# SparkFun_Buck_Regulator_-_AP63203.net
KiCad netlist of a schematic drawn in EAGLE
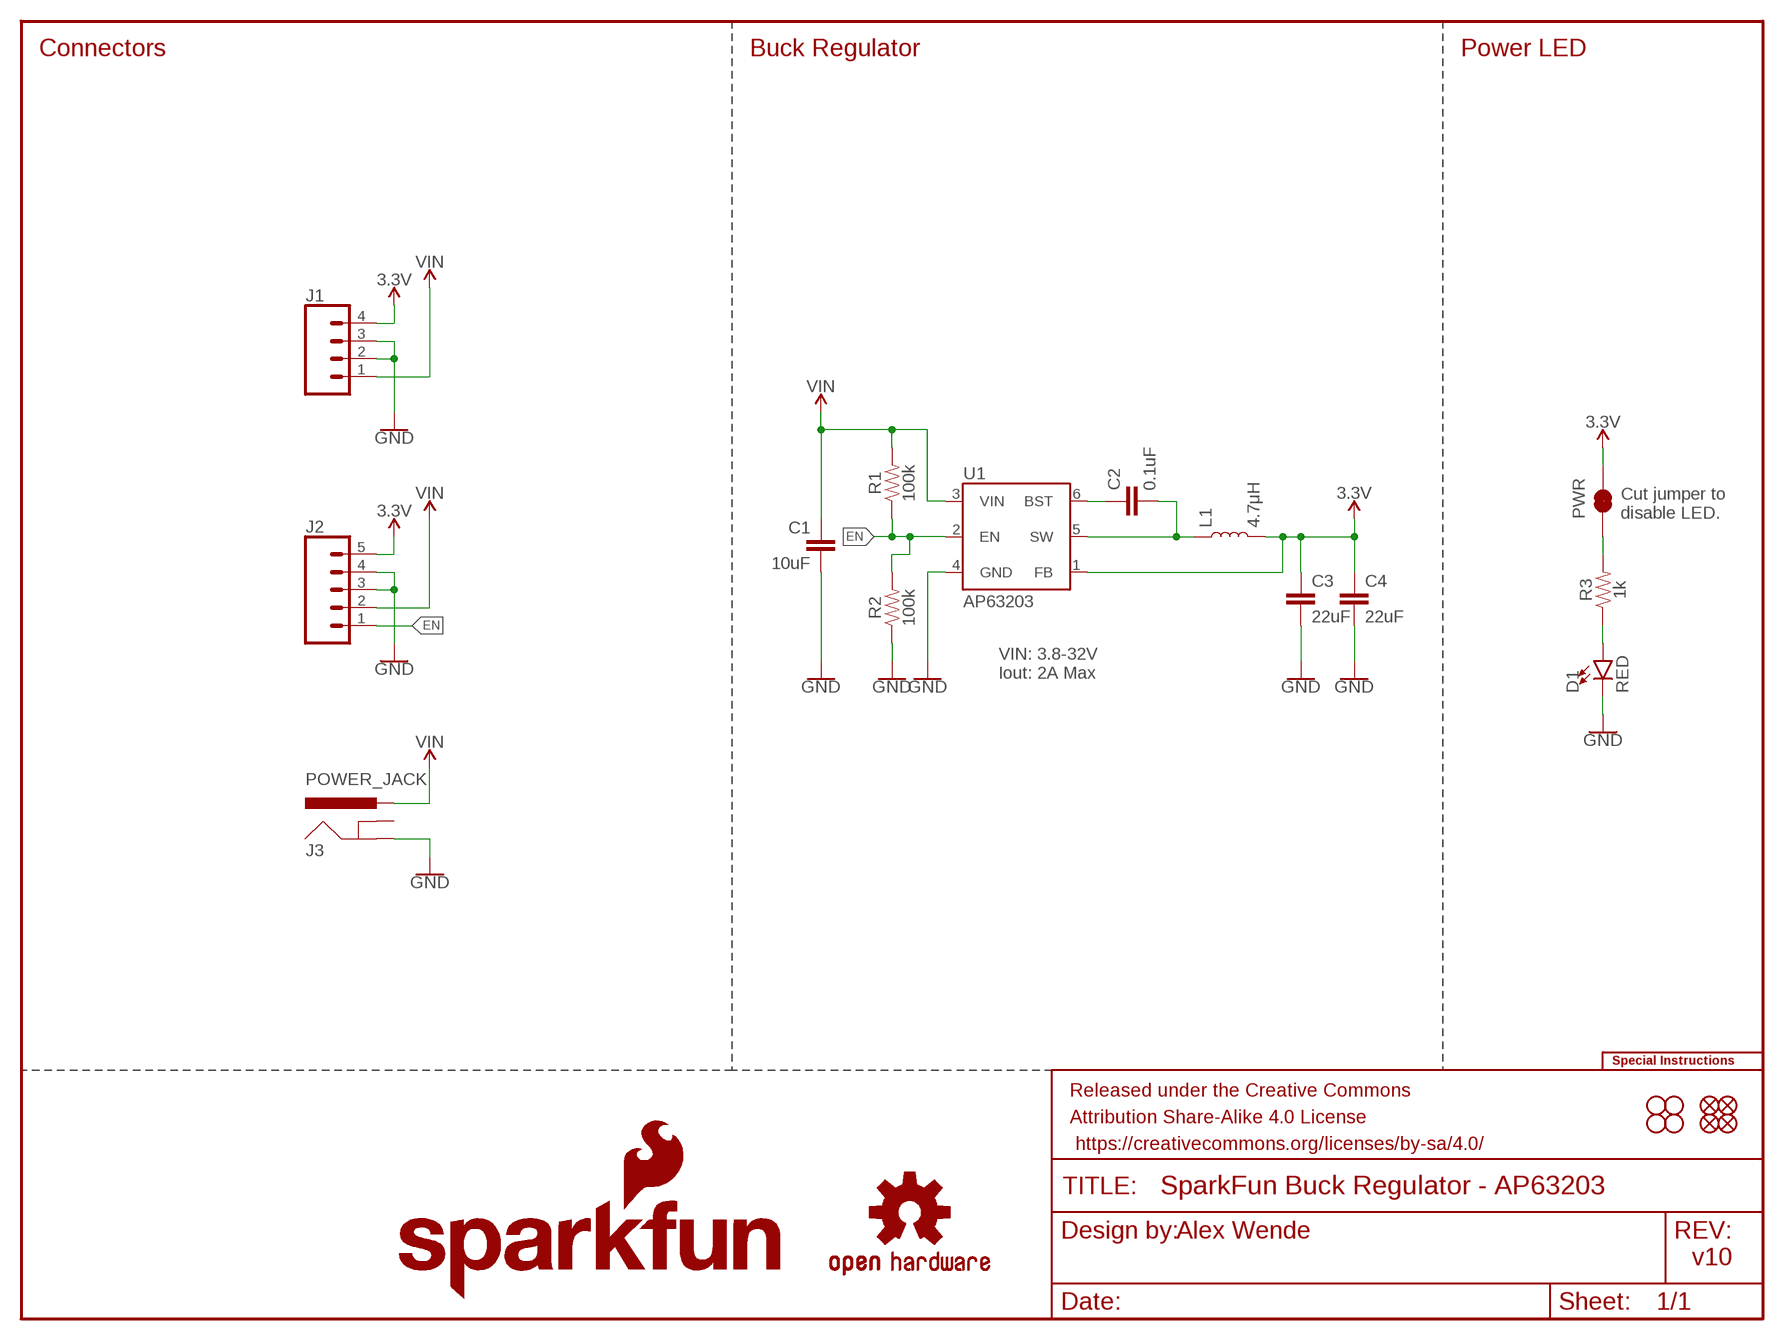
[diagram p0: schematic, sheet 1]

(export (version "E")
  (design (tool "Eeschema 10.0.6"))
  (components
    (comp (ref "C1")
      (value "10uF")
      (footprint "eagle-import:1210")
      (libsource (lib "eagle-import") (part "10UF-1210-50V-20%"))
    )
    (comp (ref "C2")
      (value "0.1uF")
      (footprint "eagle-import:0603")
      (libsource (lib "eagle-import") (part "0.1UF-0603-25V-5%"))
    )
    (comp (ref "C3")
      (value "22uF")
      (footprint "eagle-import:0603")
      (libsource (lib "eagle-import") (part "22UF-0603-6.3V-20%"))
    )
    (comp (ref "C4")
      (value "22uF")
      (footprint "eagle-import:0603")
      (libsource (lib "eagle-import") (part "22UF-0603-6.3V-20%"))
    )
    (comp (ref "D1")
      (value "RED")
      (footprint "eagle-import:LED-0603")
      (libsource (lib "eagle-import") (part "LED-RED0603"))
    )
    (comp (ref "FD1")
      (value "FIDUCIALUFIDUCIAL")
      (footprint "eagle-import:FIDUCIAL-MICRO")
      (libsource (lib "eagle-import") (part "FIDUCIALUFIDUCIAL"))
    )
    (comp (ref "FD2")
      (value "FIDUCIALUFIDUCIAL")
      (footprint "eagle-import:FIDUCIAL-MICRO")
      (libsource (lib "eagle-import") (part "FIDUCIALUFIDUCIAL"))
    )
    (comp (ref "FD3")
      (value "FIDUCIALUFIDUCIAL")
      (footprint "eagle-import:FIDUCIAL-MICRO")
      (libsource (lib "eagle-import") (part "FIDUCIALUFIDUCIAL"))
    )
    (comp (ref "FD4")
      (value "FIDUCIALUFIDUCIAL")
      (footprint "eagle-import:FIDUCIAL-MICRO")
      (libsource (lib "eagle-import") (part "FIDUCIALUFIDUCIAL"))
    )
    (comp (ref "FRAME1")
      (value "FRAME-LETTER")
      (footprint "eagle-import:CREATIVE_COMMONS")
      (libsource (lib "eagle-import") (part "FRAME-LETTER"))
    )
    (comp (ref "H1")
      (value "STAND-OFF")
      (footprint "eagle-import:STAND-OFF")
      (libsource (lib "eagle-import") (part "STAND-OFF"))
    )
    (comp (ref "H2")
      (value "STAND-OFF")
      (footprint "eagle-import:STAND-OFF")
      (libsource (lib "eagle-import") (part "STAND-OFF"))
    )
    (comp (ref "H3")
      (value "STAND-OFF")
      (footprint "eagle-import:STAND-OFF")
      (libsource (lib "eagle-import") (part "STAND-OFF"))
    )
    (comp (ref "H4")
      (value "STAND-OFF")
      (footprint "eagle-import:STAND-OFF")
      (libsource (lib "eagle-import") (part "STAND-OFF"))
    )
    (comp (ref "J1")
      (value "CONN_04SCREW")
      (footprint "eagle-import:SCREWTERMINAL-3.5MM-4")
      (libsource (lib "eagle-import") (part "CONN_04SCREW"))
    )
    (comp (ref "J2")
      (value "CONN_05NO_SILK")
      (footprint "eagle-import:1X05_NO_SILK")
      (libsource (lib "eagle-import") (part "CONN_05NO_SILK"))
    )
    (comp (ref "J3")
      (value "POWER_JACK")
      (footprint "eagle-import:POWER_JACK_PTH_SLOT")
      (libsource (lib "eagle-import") (part "POWER_JACKPOWER_JACK_SLOT"))
    )
    (comp (ref "L1")
      (value "4.7μH")
      (footprint "eagle-import:INDUCTOR_4X4MM")
      (libsource (lib "eagle-import") (part "4.7μH_SHIELDED_INDUCTORNPIS_LS"))
    )
    (comp (ref "LOGO1")
      (value "SFE_LOGO_NAME_FLAME.1_INCH")
      (footprint "eagle-import:SFE_LOGO_NAME_FLAME_.1")
      (libsource (lib "eagle-import") (part "SFE_LOGO_NAME_FLAME.1_INCH"))
    )
    (comp (ref "LOGO2")
      (value "OSHW-LOGOS")
      (footprint "eagle-import:OSHW-LOGO-S")
      (libsource (lib "eagle-import") (part "OSHW-LOGOS"))
    )
    (comp (ref "LOGO3")
      (value "SPECIAL_INSTRUCTIONS-ORDERING")
      (footprint "eagle-import:ORDERING_INSTRUCTIONS")
      (libsource (lib "eagle-import") (part "SPECIAL_INSTRUCTIONS-ORDERING"))
    )
    (comp (ref "PWR")
      (value "JUMPER-SMT_2_NC_TRACE_SILK")
      (footprint "eagle-import:SMT-JUMPER_2_NC_TRACE_SILK")
      (libsource (lib "eagle-import") (part "JUMPER-SMT_2_NC_TRACE_SILK"))
    )
    (comp (ref "R1")
      (value "100k")
      (footprint "eagle-import:0603")
      (libsource (lib "eagle-import") (part "100KOHM-0603-1/10W-1%"))
    )
    (comp (ref "R2")
      (value "100k")
      (footprint "eagle-import:0603")
      (libsource (lib "eagle-import") (part "100KOHM-0603-1/10W-1%"))
    )
    (comp (ref "R3")
      (value "1k")
      (footprint "eagle-import:0603")
      (libsource (lib "eagle-import") (part "1KOHM-0603-1/10W-1%"))
    )
    (comp (ref "U1")
      (value "AP63203")
      (footprint "eagle-import:SOT23-6")
      (libsource (lib "eagle-import") (part "AP63203"))
    )
  )
  (nets
    (net (code "1") (name "3.3V") (class "Default")
      (node (ref "C3") (pin "1") (pinfunction "1_1") (pintype "passive"))
      (node (ref "C4") (pin "1") (pinfunction "1_1") (pintype "passive"))
      (node (ref "J1") (pin "4") (pinfunction "4_4") (pintype "passive"))
      (node (ref "J2") (pin "5") (pinfunction "5_5") (pintype "passive"))
      (node (ref "L1") (pin "P$2") (pinfunction "2_P$2") (pintype "passive"))
      (node (ref "PWR") (pin "2") (pinfunction "2_2") (pintype "passive"))
      (node (ref "U1") (pin "1") (pinfunction "FB_1") (pintype "bidirectional"))
    )
    (net (code "2") (name "EN") (class "Default")
      (node (ref "J2") (pin "1") (pinfunction "1_1") (pintype "passive"))
      (node (ref "R1") (pin "1") (pinfunction "1_1") (pintype "passive"))
      (node (ref "R2") (pin "2") (pinfunction "2_2") (pintype "passive"))
      (node (ref "U1") (pin "2") (pinfunction "EN_2") (pintype "bidirectional"))
    )
    (net (code "3") (name "GND") (class "Default")
      (node (ref "C1") (pin "2") (pinfunction "2_2") (pintype "passive"))
      (node (ref "C3") (pin "2") (pinfunction "2_2") (pintype "passive"))
      (node (ref "C4") (pin "2") (pinfunction "2_2") (pintype "passive"))
      (node (ref "D1") (pin "C") (pinfunction "C_C") (pintype "passive"))
      (node (ref "J1") (pin "2") (pinfunction "2_2") (pintype "passive"))
      (node (ref "J1") (pin "3") (pinfunction "3_3") (pintype "passive"))
      (node (ref "J2") (pin "3") (pinfunction "3_3") (pintype "passive"))
      (node (ref "J2") (pin "4") (pinfunction "4_4") (pintype "passive"))
      (node (ref "J3") (pin "GND") (pinfunction "GND_GND") (pintype "bidirectional"))
      (node (ref "R2") (pin "1") (pinfunction "1_1") (pintype "passive"))
      (node (ref "U1") (pin "4") (pinfunction "GND_4") (pintype "bidirectional"))
    )
    (net (code "4") (name "Net-(D1-PadA)") (class "Default")
      (node (ref "D1") (pin "A") (pinfunction "A_A") (pintype "passive"))
      (node (ref "R3") (pin "1") (pinfunction "1_1") (pintype "passive"))
    )
    (net (code "5") (name "Net-(L1-1)") (class "Default")
      (node (ref "C2") (pin "2") (pinfunction "2_2") (pintype "passive"))
      (node (ref "L1") (pin "P$1") (pinfunction "1_P$1") (pintype "passive"))
      (node (ref "U1") (pin "5") (pinfunction "SW_5") (pintype "bidirectional"))
    )
    (net (code "6") (name "Net-(PWR-Pad1)") (class "Default")
      (node (ref "PWR") (pin "1") (pinfunction "1_1") (pintype "passive"))
      (node (ref "R3") (pin "2") (pinfunction "2_2") (pintype "passive"))
    )
    (net (code "7") (name "Net-(U1-BST)") (class "Default")
      (node (ref "C2") (pin "1") (pinfunction "1_1") (pintype "passive"))
      (node (ref "U1") (pin "6") (pinfunction "BST_6") (pintype "bidirectional"))
    )
    (net (code "8") (name "VIN") (class "Default")
      (node (ref "C1") (pin "1") (pinfunction "1_1") (pintype "passive"))
      (node (ref "J1") (pin "1") (pinfunction "1_1") (pintype "passive"))
      (node (ref "J2") (pin "2") (pinfunction "2_2") (pintype "passive"))
      (node (ref "J3") (pin "PWR") (pinfunction "PWR_PWR") (pintype "bidirectional"))
      (node (ref "R1") (pin "2") (pinfunction "2_2") (pintype "passive"))
      (node (ref "U1") (pin "3") (pinfunction "VIN_3") (pintype "bidirectional"))
    )
    (net (code "9") (name "unconnected-(J3-PadGNDBREAK)") (class "Default")
      (node (ref "J3") (pin "GNDBREAK") (pinfunction "GNDBREAK_GNDBREAK") (pintype "bidirectional"))
    )
  )
)
